# atarimovie.net
KiCad netlist of a schematic drawn in EAGLE
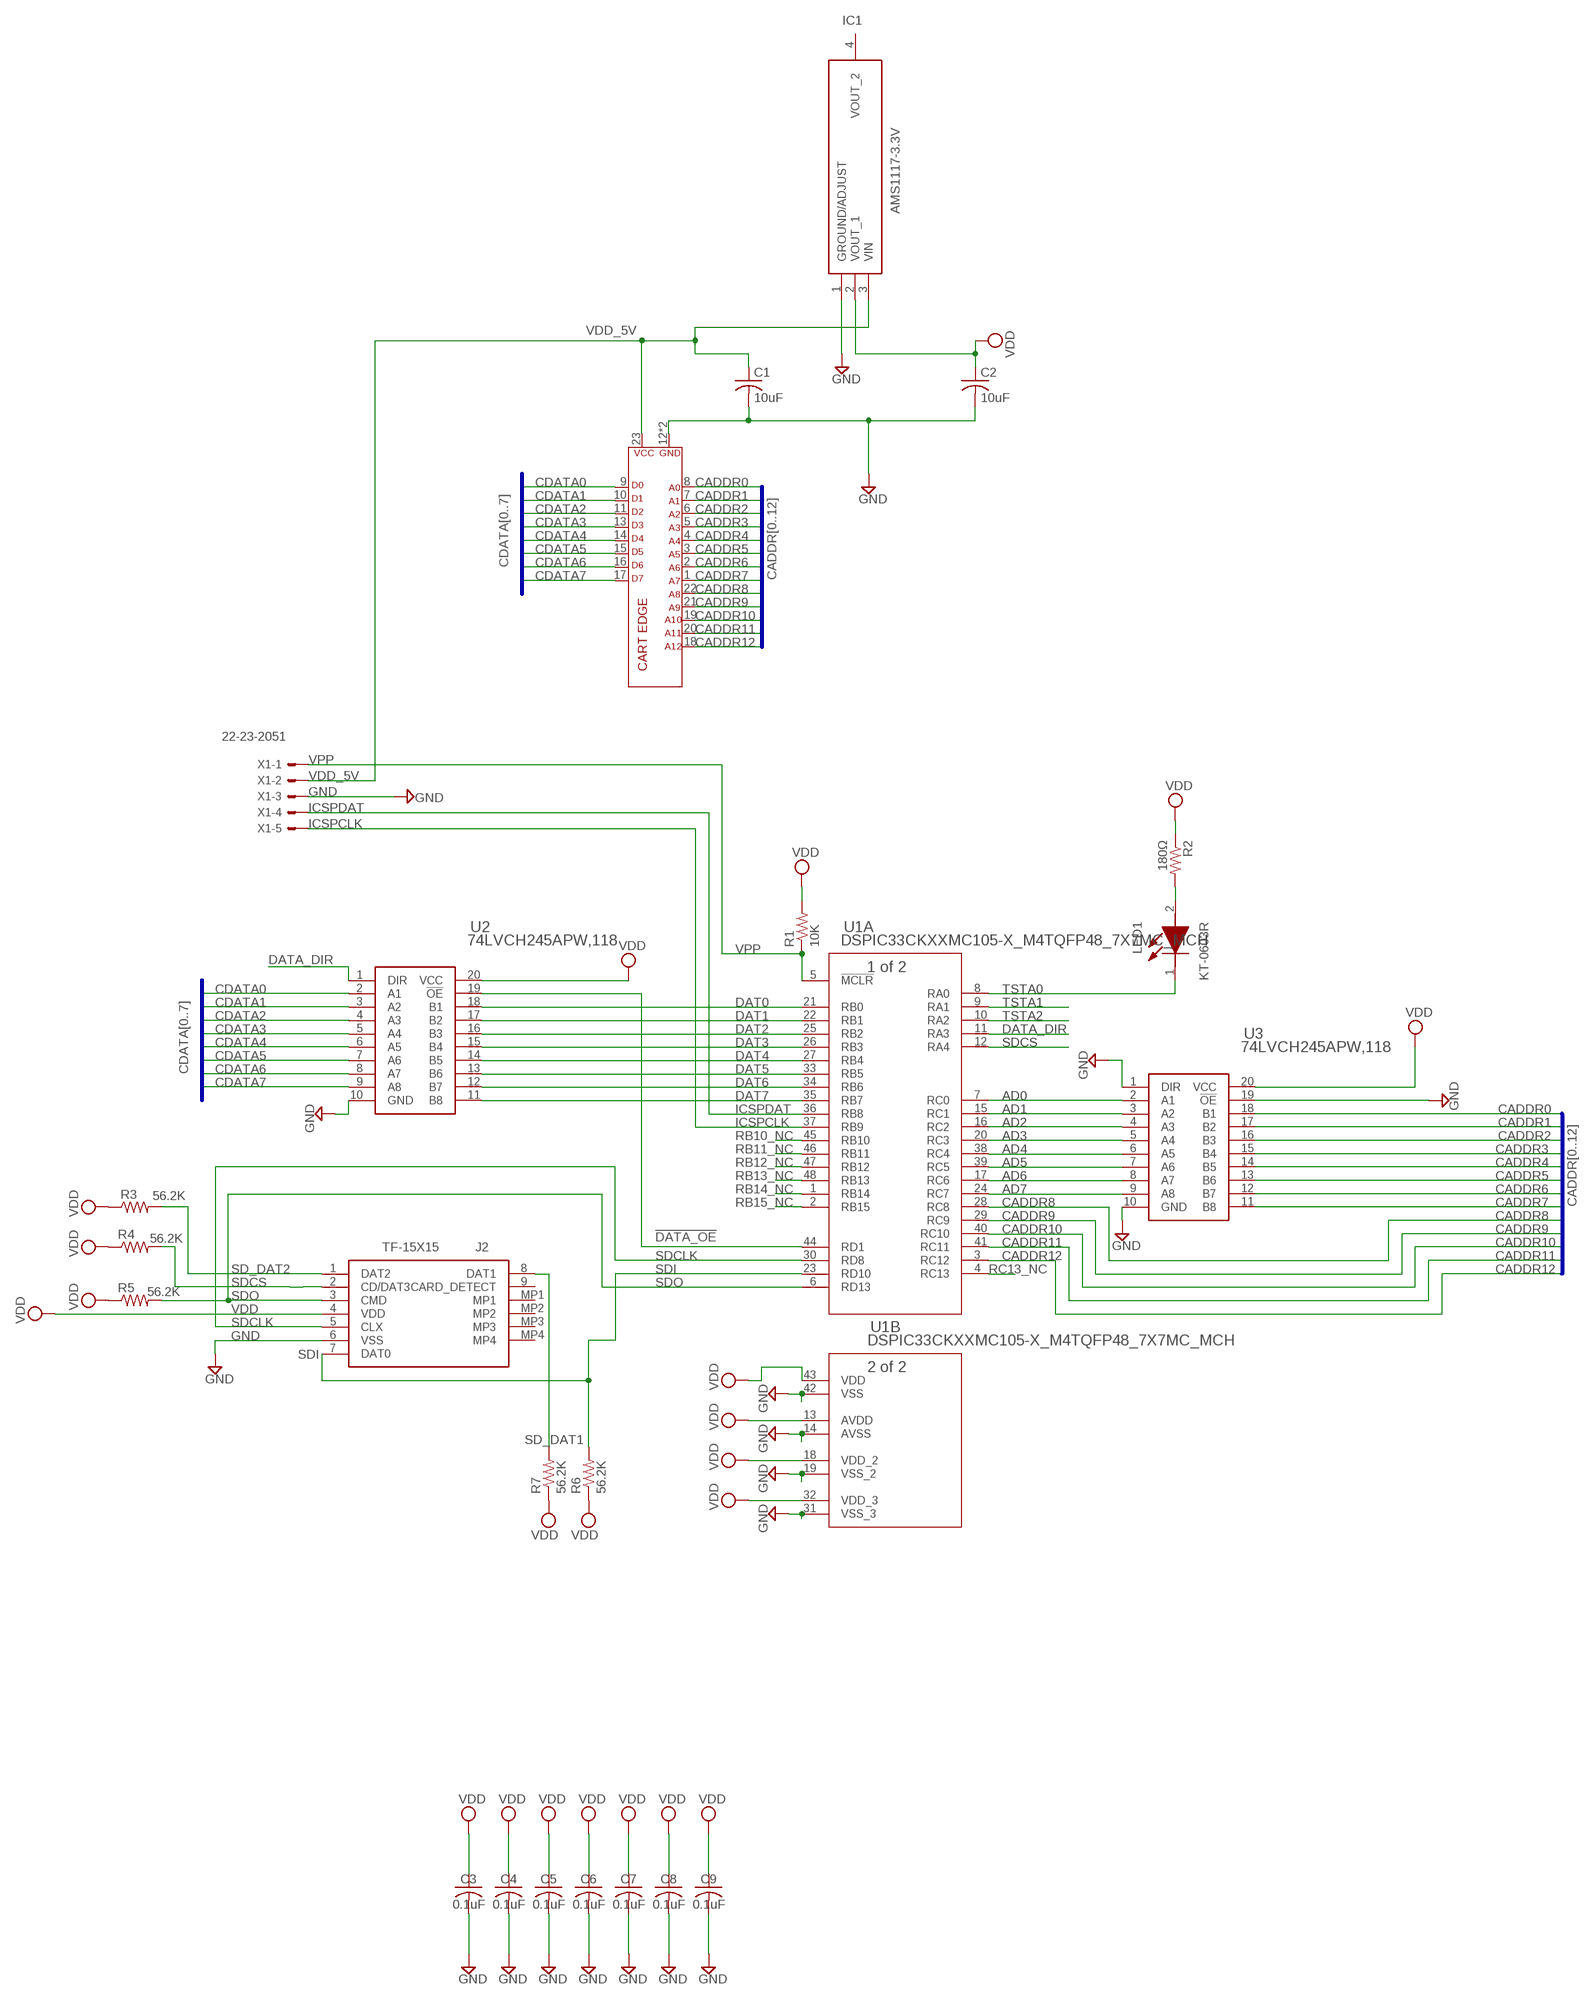
[diagram p0: schematic, sheet 1]

(export (version "E")
  (design (tool "Eeschema 10.0.6"))
  (components
    (comp (ref "C1")
      (value "10uF")
      (footprint "eagle-import:C0603K")
      (libsource (lib "eagle-import") (part "C-USC0603K"))
    )
    (comp (ref "C2")
      (value "10uF")
      (footprint "eagle-import:C0603K")
      (libsource (lib "eagle-import") (part "C-USC0603K"))
    )
    (comp (ref "C3")
      (value "0.1uF")
      (footprint "eagle-import:C0603K")
      (libsource (lib "eagle-import") (part "C-USC0603K"))
    )
    (comp (ref "C4")
      (value "0.1uF")
      (footprint "eagle-import:C0603K")
      (libsource (lib "eagle-import") (part "C-USC0603K"))
    )
    (comp (ref "C5")
      (value "0.1uF")
      (footprint "eagle-import:C0603K")
      (libsource (lib "eagle-import") (part "C-USC0603K"))
    )
    (comp (ref "C6")
      (value "0.1uF")
      (footprint "eagle-import:C0603K")
      (libsource (lib "eagle-import") (part "C-USC0603K"))
    )
    (comp (ref "C7")
      (value "0.1uF")
      (footprint "eagle-import:C0603K")
      (libsource (lib "eagle-import") (part "C-USC0603K"))
    )
    (comp (ref "C8")
      (value "0.1uF")
      (footprint "eagle-import:C0603K")
      (libsource (lib "eagle-import") (part "C-USC0603K"))
    )
    (comp (ref "C9")
      (value "0.1uF")
      (footprint "eagle-import:C0603K")
      (libsource (lib "eagle-import") (part "C-USC0603K"))
    )
    (comp (ref "IC1")
      (value "AMS1117-3.3V")
      (footprint "eagle-import:SOT229P700X180-4N")
      (fields (field (name "MANUFACTURER_PART_NUMBER") "ams1117-3.3v"))
      (libsource (lib "eagle-import") (part "AMS1117-3.3V"))
    )
    (comp (ref "J1")
      (value "CARTRIDGE EDGE")
      (footprint "eagle-import:MED_TABS_SHORT")
      (libsource (lib "eagle-import") (part "ATARI-2600MED_TABS_SHORT"))
    )
    (comp (ref "J2")
      (value "TF-15X15")
      (footprint "eagle-import:TF15X15")
      (libsource (lib "eagle-import") (part "TF-15X15"))
    )
    (comp (ref "LED1")
      (value "KT-0603R")
      (footprint "eagle-import:LEDC1608X70N")
      (libsource (lib "eagle-import") (part "KT-0603R"))
    )
    (comp (ref "R1")
      (value "10K")
      (footprint "eagle-import:R0603")
      (libsource (lib "eagle-import") (part "R-US_R0603"))
    )
    (comp (ref "R2")
      (value "180Ω")
      (footprint "eagle-import:R0603")
      (libsource (lib "eagle-import") (part "R-US_R0603"))
    )
    (comp (ref "R3")
      (value "56.2K")
      (footprint "eagle-import:R0603")
      (libsource (lib "eagle-import") (part "R-US_R0603"))
    )
    (comp (ref "R4")
      (value "56.2K")
      (footprint "eagle-import:R0603")
      (libsource (lib "eagle-import") (part "R-US_R0603"))
    )
    (comp (ref "R5")
      (value "56.2K")
      (footprint "eagle-import:R0603")
      (libsource (lib "eagle-import") (part "R-US_R0603"))
    )
    (comp (ref "R6")
      (value "56.2K")
      (footprint "eagle-import:R0603")
      (libsource (lib "eagle-import") (part "R-US_R0603"))
    )
    (comp (ref "R7")
      (value "56.2K")
      (footprint "eagle-import:R0603")
      (libsource (lib "eagle-import") (part "R-US_R0603"))
    )
    (comp (ref "U1")
      (value "DSPIC33CKXXMC105-X_M4TQFP48_7X7MC_MCH")
      (footprint "eagle-import:TQFP48_7X7MC_MCH")
      (libsource (lib "eagle-import") (part "DSPIC33CKXXMC105-X_M4TQFP48_7X7MC_MCH"))
    )
    (comp (ref "U2")
      (value "74LVCH245APW,118")
      (footprint "eagle-import:SOP65P640X110-20N")
      (fields (field (name "MOUSER_PART_NUMBER") "771-74LVCH245APW-T"))
      (libsource (lib "eagle-import") (part "74LVCH245APW,118"))
    )
    (comp (ref "U3")
      (value "74LVCH245APW,118")
      (footprint "eagle-import:SOP65P640X110-20N")
      (fields (field (name "MOUSER_PART_NUMBER") "771-74LVCH245APW-T"))
      (libsource (lib "eagle-import") (part "74LVCH245APW,118"))
    )
    (comp (ref "X1")
      (value "22-23-2051")
      (footprint "eagle-import:22-23-2051")
      (fields (field (name "MF") "MOLEX"))
      (libsource (lib "eagle-import") (part "22-23-2051"))
    )
  )
  (nets
    (net (code "1") (name "/AD0") (class "Default")
      (node (ref "U1") (pin "7") (pinfunction "RC0_7") (pintype "bidirectional"))
      (node (ref "U3") (pin "2") (pinfunction "A1_2") (pintype "bidirectional"))
    )
    (net (code "2") (name "/AD1") (class "Default")
      (node (ref "U1") (pin "15") (pinfunction "RC1_15") (pintype "bidirectional"))
      (node (ref "U3") (pin "3") (pinfunction "A2_3") (pintype "bidirectional"))
    )
    (net (code "3") (name "/AD2") (class "Default")
      (node (ref "U1") (pin "16") (pinfunction "RC2_16") (pintype "bidirectional"))
      (node (ref "U3") (pin "4") (pinfunction "A3_4") (pintype "bidirectional"))
    )
    (net (code "4") (name "/AD3") (class "Default")
      (node (ref "U1") (pin "20") (pinfunction "RC3_20") (pintype "bidirectional"))
      (node (ref "U3") (pin "5") (pinfunction "A4_5") (pintype "bidirectional"))
    )
    (net (code "5") (name "/AD4") (class "Default")
      (node (ref "U1") (pin "38") (pinfunction "RC4_38") (pintype "bidirectional"))
      (node (ref "U3") (pin "6") (pinfunction "A5_6") (pintype "bidirectional"))
    )
    (net (code "6") (name "/AD5") (class "Default")
      (node (ref "U1") (pin "39") (pinfunction "RC5_39") (pintype "bidirectional"))
      (node (ref "U3") (pin "7") (pinfunction "A6_7") (pintype "bidirectional"))
    )
    (net (code "7") (name "/AD6") (class "Default")
      (node (ref "U1") (pin "17") (pinfunction "RC6_17") (pintype "bidirectional"))
      (node (ref "U3") (pin "8") (pinfunction "A7_8") (pintype "bidirectional"))
    )
    (net (code "8") (name "/AD7") (class "Default")
      (node (ref "U1") (pin "24") (pinfunction "RC7_24") (pintype "bidirectional"))
      (node (ref "U3") (pin "9") (pinfunction "A8_9") (pintype "bidirectional"))
    )
    (net (code "9") (name "/CADDR0") (class "Default")
      (node (ref "J1") (pin "8") (pinfunction "A0_8") (pintype "bidirectional"))
      (node (ref "U3") (pin "18") (pinfunction "B1_18") (pintype "bidirectional"))
    )
    (net (code "10") (name "/CADDR1") (class "Default")
      (node (ref "J1") (pin "7") (pinfunction "A1_7") (pintype "bidirectional"))
      (node (ref "U3") (pin "17") (pinfunction "B2_17") (pintype "bidirectional"))
    )
    (net (code "11") (name "/CADDR2") (class "Default")
      (node (ref "J1") (pin "6") (pinfunction "A2_6") (pintype "bidirectional"))
      (node (ref "U3") (pin "16") (pinfunction "B3_16") (pintype "bidirectional"))
    )
    (net (code "12") (name "/CADDR3") (class "Default")
      (node (ref "J1") (pin "5") (pinfunction "A3_5") (pintype "bidirectional"))
      (node (ref "U3") (pin "15") (pinfunction "B4_15") (pintype "bidirectional"))
    )
    (net (code "13") (name "/CADDR4") (class "Default")
      (node (ref "J1") (pin "4") (pinfunction "A4_4") (pintype "bidirectional"))
      (node (ref "U3") (pin "14") (pinfunction "B5_14") (pintype "bidirectional"))
    )
    (net (code "14") (name "/CADDR5") (class "Default")
      (node (ref "J1") (pin "3") (pinfunction "A5_3") (pintype "bidirectional"))
      (node (ref "U3") (pin "13") (pinfunction "B6_13") (pintype "bidirectional"))
    )
    (net (code "15") (name "/CADDR6") (class "Default")
      (node (ref "J1") (pin "2") (pinfunction "A6_2") (pintype "bidirectional"))
      (node (ref "U3") (pin "12") (pinfunction "B7_12") (pintype "bidirectional"))
    )
    (net (code "16") (name "/CADDR7") (class "Default")
      (node (ref "J1") (pin "1") (pinfunction "A7_1") (pintype "bidirectional"))
      (node (ref "U3") (pin "11") (pinfunction "B8_11") (pintype "bidirectional"))
    )
    (net (code "17") (name "/CADDR8") (class "Default")
      (node (ref "J1") (pin "22") (pinfunction "A8_22") (pintype "bidirectional"))
      (node (ref "U1") (pin "28") (pinfunction "RC8_28") (pintype "bidirectional"))
    )
    (net (code "18") (name "/CADDR9") (class "Default")
      (node (ref "J1") (pin "21") (pinfunction "A9_21") (pintype "bidirectional"))
      (node (ref "U1") (pin "29") (pinfunction "RC9_29") (pintype "bidirectional"))
    )
    (net (code "19") (name "/CADDR10") (class "Default")
      (node (ref "J1") (pin "19") (pinfunction "A10_19") (pintype "bidirectional"))
      (node (ref "U1") (pin "40") (pinfunction "RC10_40") (pintype "bidirectional"))
    )
    (net (code "20") (name "/CADDR11") (class "Default")
      (node (ref "J1") (pin "20") (pinfunction "A11_20") (pintype "bidirectional"))
      (node (ref "U1") (pin "41") (pinfunction "RC11_41") (pintype "bidirectional"))
    )
    (net (code "21") (name "/CADDR12") (class "Default")
      (node (ref "J1") (pin "18") (pinfunction "A12_18") (pintype "bidirectional"))
      (node (ref "U1") (pin "3") (pinfunction "RC12_3") (pintype "bidirectional"))
    )
    (net (code "23") (name "/CDATA0") (class "Default")
      (node (ref "J1") (pin "9") (pinfunction "D0_9") (pintype "bidirectional"))
      (node (ref "U2") (pin "2") (pinfunction "A1_2") (pintype "bidirectional"))
    )
    (net (code "24") (name "/CDATA1") (class "Default")
      (node (ref "J1") (pin "10") (pinfunction "D1_10") (pintype "bidirectional"))
      (node (ref "U2") (pin "3") (pinfunction "A2_3") (pintype "bidirectional"))
    )
    (net (code "25") (name "/CDATA2") (class "Default")
      (node (ref "J1") (pin "11") (pinfunction "D2_11") (pintype "bidirectional"))
      (node (ref "U2") (pin "4") (pinfunction "A3_4") (pintype "bidirectional"))
    )
    (net (code "26") (name "/CDATA3") (class "Default")
      (node (ref "J1") (pin "13") (pinfunction "D3_13") (pintype "bidirectional"))
      (node (ref "U2") (pin "5") (pinfunction "A4_5") (pintype "bidirectional"))
    )
    (net (code "27") (name "/CDATA4") (class "Default")
      (node (ref "J1") (pin "14") (pinfunction "D4_14") (pintype "bidirectional"))
      (node (ref "U2") (pin "6") (pinfunction "A5_6") (pintype "bidirectional"))
    )
    (net (code "28") (name "/CDATA5") (class "Default")
      (node (ref "J1") (pin "15") (pinfunction "D5_15") (pintype "bidirectional"))
      (node (ref "U2") (pin "7") (pinfunction "A6_7") (pintype "bidirectional"))
    )
    (net (code "29") (name "/CDATA6") (class "Default")
      (node (ref "J1") (pin "16") (pinfunction "D6_16") (pintype "bidirectional"))
      (node (ref "U2") (pin "8") (pinfunction "A7_8") (pintype "bidirectional"))
    )
    (net (code "30") (name "/CDATA7") (class "Default")
      (node (ref "J1") (pin "17") (pinfunction "D7_17") (pintype "bidirectional"))
      (node (ref "U2") (pin "9") (pinfunction "A8_9") (pintype "bidirectional"))
    )
    (net (code "32") (name "/DAT0") (class "Default")
      (node (ref "U1") (pin "21") (pinfunction "RB0_21") (pintype "bidirectional"))
      (node (ref "U2") (pin "18") (pinfunction "B1_18") (pintype "bidirectional"))
    )
    (net (code "33") (name "/DAT1") (class "Default")
      (node (ref "U1") (pin "22") (pinfunction "RB1_22") (pintype "bidirectional"))
      (node (ref "U2") (pin "17") (pinfunction "B2_17") (pintype "bidirectional"))
    )
    (net (code "34") (name "/DAT2") (class "Default")
      (node (ref "U1") (pin "25") (pinfunction "RB2_25") (pintype "bidirectional"))
      (node (ref "U2") (pin "16") (pinfunction "B3_16") (pintype "bidirectional"))
    )
    (net (code "35") (name "/DAT3") (class "Default")
      (node (ref "U1") (pin "26") (pinfunction "RB3_26") (pintype "bidirectional"))
      (node (ref "U2") (pin "15") (pinfunction "B4_15") (pintype "bidirectional"))
    )
    (net (code "36") (name "/DAT4") (class "Default")
      (node (ref "U1") (pin "27") (pinfunction "RB4_27") (pintype "bidirectional"))
      (node (ref "U2") (pin "14") (pinfunction "B5_14") (pintype "bidirectional"))
    )
    (net (code "37") (name "/DAT5") (class "Default")
      (node (ref "U1") (pin "33") (pinfunction "RB5_33") (pintype "bidirectional"))
      (node (ref "U2") (pin "13") (pinfunction "B6_13") (pintype "bidirectional"))
    )
    (net (code "38") (name "/DAT6") (class "Default")
      (node (ref "U1") (pin "34") (pinfunction "RB6_34") (pintype "bidirectional"))
      (node (ref "U2") (pin "12") (pinfunction "B7_12") (pintype "bidirectional"))
    )
    (net (code "39") (name "/DAT7") (class "Default")
      (node (ref "U1") (pin "35") (pinfunction "RB7_35") (pintype "bidirectional"))
      (node (ref "U2") (pin "11") (pinfunction "B8_11") (pintype "bidirectional"))
    )
    (net (code "40") (name "/DATA_DIR") (class "Default")
      (node (ref "U1") (pin "11") (pinfunction "RA3_11") (pintype "bidirectional"))
      (node (ref "U2") (pin "1") (pinfunction "DIR_1") (pintype "bidirectional"))
    )
    (net (code "41") (name "/ICSPCLK") (class "Default")
      (node (ref "U1") (pin "37") (pinfunction "RB9_37") (pintype "bidirectional"))
      (node (ref "X1") (pin "5") (pinfunction "S_5") (pintype "passive"))
    )
    (net (code "42") (name "/ICSPDAT") (class "Default")
      (node (ref "U1") (pin "36") (pinfunction "RB8_36") (pintype "bidirectional"))
      (node (ref "X1") (pin "4") (pinfunction "S_4") (pintype "passive"))
    )
    (net (code "43") (name "/RB10_NC") (class "Default")
      (node (ref "U1") (pin "45") (pinfunction "RB10_45") (pintype "bidirectional"))
    )
    (net (code "44") (name "/RB11_NC") (class "Default")
      (node (ref "U1") (pin "46") (pinfunction "RB11_46") (pintype "bidirectional"))
    )
    (net (code "45") (name "/RB12_NC") (class "Default")
      (node (ref "U1") (pin "47") (pinfunction "RB12_47") (pintype "bidirectional"))
    )
    (net (code "46") (name "/RB13_NC") (class "Default")
      (node (ref "U1") (pin "48") (pinfunction "RB13_48") (pintype "bidirectional"))
    )
    (net (code "47") (name "/RB14_NC") (class "Default")
      (node (ref "U1") (pin "1") (pinfunction "RB14_1") (pintype "bidirectional"))
    )
    (net (code "48") (name "/RB15_NC") (class "Default")
      (node (ref "U1") (pin "2") (pinfunction "RB15_2") (pintype "bidirectional"))
    )
    (net (code "49") (name "/RC13_NC") (class "Default")
      (node (ref "U1") (pin "4") (pinfunction "RC13_4") (pintype "bidirectional"))
    )
    (net (code "50") (name "/SDCLK") (class "Default")
      (node (ref "J2") (pin "5") (pinfunction "CLX_5") (pintype "bidirectional"))
      (node (ref "U1") (pin "30") (pinfunction "RD8_30") (pintype "bidirectional"))
    )
    (net (code "51") (name "/SDCS") (class "Default")
      (node (ref "J2") (pin "2") (pinfunction "CD/DAT3_2") (pintype "bidirectional"))
      (node (ref "R4") (pin "2") (pinfunction "2_2") (pintype "passive"))
      (node (ref "U1") (pin "12") (pinfunction "RA4_12") (pintype "bidirectional"))
    )
    (net (code "52") (name "/SDI") (class "Default")
      (node (ref "J2") (pin "7") (pinfunction "DAT0_7") (pintype "bidirectional"))
      (node (ref "R6") (pin "2") (pinfunction "2_2") (pintype "passive"))
      (node (ref "U1") (pin "23") (pinfunction "RD10_23") (pintype "bidirectional"))
    )
    (net (code "53") (name "/SDO") (class "Default")
      (node (ref "J2") (pin "3") (pinfunction "CMD_3") (pintype "bidirectional"))
      (node (ref "R5") (pin "2") (pinfunction "2_2") (pintype "passive"))
      (node (ref "U1") (pin "6") (pinfunction "RD13_6") (pintype "bidirectional"))
    )
    (net (code "54") (name "/SD_DAT1") (class "Default")
      (node (ref "J2") (pin "8") (pinfunction "DAT1_8") (pintype "bidirectional"))
      (node (ref "R7") (pin "2") (pinfunction "2_2") (pintype "passive"))
    )
    (net (code "55") (name "/SD_DAT2") (class "Default")
      (node (ref "J2") (pin "1") (pinfunction "DAT2_1") (pintype "bidirectional"))
      (node (ref "R3") (pin "2") (pinfunction "2_2") (pintype "passive"))
    )
    (net (code "56") (name "/TSTA0") (class "Default")
      (node (ref "LED1") (pin "1") (pinfunction "K_1") (pintype "bidirectional"))
      (node (ref "U1") (pin "8") (pinfunction "RA0_8") (pintype "bidirectional"))
    )
    (net (code "57") (name "/TSTA1") (class "Default")
      (node (ref "U1") (pin "9") (pinfunction "RA1_9") (pintype "bidirectional"))
    )
    (net (code "58") (name "/TSTA2") (class "Default")
      (node (ref "U1") (pin "10") (pinfunction "RA2_10") (pintype "bidirectional"))
    )
    (net (code "59") (name "/VDD_5V") (class "Default")
      (node (ref "C1") (pin "1") (pinfunction "1_1") (pintype "passive"))
      (node (ref "IC1") (pin "3") (pinfunction "VIN_3") (pintype "bidirectional"))
      (node (ref "J1") (pin "23") (pinfunction "VCC_23") (pintype "power_in"))
      (node (ref "X1") (pin "2") (pinfunction "S_2") (pintype "passive"))
    )
    (net (code "60") (name "/VPP") (class "Default")
      (node (ref "R1") (pin "1") (pinfunction "1_1") (pintype "passive"))
      (node (ref "U1") (pin "5") (pinfunction "~{MCLR}_5") (pintype "input"))
      (node (ref "X1") (pin "1") (pinfunction "S_1") (pintype "passive"))
    )
    (net (code "61") (name "/~{DATA_OE}") (class "Default")
      (node (ref "U1") (pin "44") (pinfunction "RD1_44") (pintype "bidirectional"))
      (node (ref "U2") (pin "19") (pinfunction "~{OE}_19") (pintype "bidirectional"))
    )
    (net (code "62") (name "GND") (class "Default")
      (node (ref "C1") (pin "2") (pinfunction "2_2") (pintype "passive"))
      (node (ref "C2") (pin "2") (pinfunction "2_2") (pintype "passive"))
      (node (ref "C3") (pin "2") (pinfunction "2_2") (pintype "passive"))
      (node (ref "C4") (pin "2") (pinfunction "2_2") (pintype "passive"))
      (node (ref "C5") (pin "2") (pinfunction "2_2") (pintype "passive"))
      (node (ref "C6") (pin "2") (pinfunction "2_2") (pintype "passive"))
      (node (ref "C7") (pin "2") (pinfunction "2_2") (pintype "passive"))
      (node (ref "C8") (pin "2") (pinfunction "2_2") (pintype "passive"))
      (node (ref "C9") (pin "2") (pinfunction "2_2") (pintype "passive"))
      (node (ref "IC1") (pin "1") (pinfunction "GROUND/ADJUST_1") (pintype "bidirectional"))
      (node (ref "J1") (pin "12") (pinfunction "GND_12") (pintype "power_in"))
      (node (ref "J1") (pin "24") (pinfunction "GND_24") (pintype "power_in"))
      (node (ref "J2") (pin "6") (pinfunction "VSS_6") (pintype "bidirectional"))
      (node (ref "U1") (pin "14") (pinfunction "AVSS_14") (pintype "power_in"))
      (node (ref "U1") (pin "19") (pinfunction "VSS_2_19") (pintype "power_in"))
      (node (ref "U1") (pin "31") (pinfunction "VSS_3_31") (pintype "power_in"))
      (node (ref "U1") (pin "42") (pinfunction "VSS_42") (pintype "power_in"))
      (node (ref "U2") (pin "10") (pinfunction "GND_10") (pintype "bidirectional"))
      (node (ref "U3") (pin "1") (pinfunction "DIR_1") (pintype "bidirectional"))
      (node (ref "U3") (pin "10") (pinfunction "GND_10") (pintype "bidirectional"))
      (node (ref "U3") (pin "19") (pinfunction "~{OE}_19") (pintype "bidirectional"))
      (node (ref "X1") (pin "3") (pinfunction "S_3") (pintype "passive"))
    )
    (net (code "63") (name "Net-(LED1-A)") (class "Default")
      (node (ref "LED1") (pin "2") (pinfunction "A_2") (pintype "bidirectional"))
      (node (ref "R2") (pin "2") (pinfunction "2_2") (pintype "passive"))
    )
    (net (code "64") (name "VDD") (class "Default")
      (node (ref "C2") (pin "1") (pinfunction "1_1") (pintype "passive"))
      (node (ref "C3") (pin "1") (pinfunction "1_1") (pintype "passive"))
      (node (ref "C4") (pin "1") (pinfunction "1_1") (pintype "passive"))
      (node (ref "C5") (pin "1") (pinfunction "1_1") (pintype "passive"))
      (node (ref "C6") (pin "1") (pinfunction "1_1") (pintype "passive"))
      (node (ref "C7") (pin "1") (pinfunction "1_1") (pintype "passive"))
      (node (ref "C8") (pin "1") (pinfunction "1_1") (pintype "passive"))
      (node (ref "C9") (pin "1") (pinfunction "1_1") (pintype "passive"))
      (node (ref "IC1") (pin "2") (pinfunction "VOUT_1_2") (pintype "bidirectional"))
      (node (ref "J2") (pin "4") (pinfunction "VDD_4") (pintype "bidirectional"))
      (node (ref "R1") (pin "2") (pinfunction "2_2") (pintype "passive"))
      (node (ref "R2") (pin "1") (pinfunction "1_1") (pintype "passive"))
      (node (ref "R3") (pin "1") (pinfunction "1_1") (pintype "passive"))
      (node (ref "R4") (pin "1") (pinfunction "1_1") (pintype "passive"))
      (node (ref "R5") (pin "1") (pinfunction "1_1") (pintype "passive"))
      (node (ref "R6") (pin "1") (pinfunction "1_1") (pintype "passive"))
      (node (ref "R7") (pin "1") (pinfunction "1_1") (pintype "passive"))
      (node (ref "U1") (pin "13") (pinfunction "AVDD_13") (pintype "power_in"))
      (node (ref "U1") (pin "18") (pinfunction "VDD_2_18") (pintype "power_in"))
      (node (ref "U1") (pin "32") (pinfunction "VDD_3_32") (pintype "power_in"))
      (node (ref "U1") (pin "43") (pinfunction "VDD_43") (pintype "power_in"))
      (node (ref "U2") (pin "20") (pinfunction "VCC_20") (pintype "bidirectional"))
      (node (ref "U3") (pin "20") (pinfunction "VCC_20") (pintype "bidirectional"))
    )
    (net (code "65") (name "unconnected-(IC1-VOUT_2-Pad4)") (class "Default")
      (node (ref "IC1") (pin "4") (pinfunction "VOUT_2_4") (pintype "bidirectional"))
    )
    (net (code "66") (name "unconnected-(J2-CARD_DETECT-Pad9)") (class "Default")
      (node (ref "J2") (pin "9") (pinfunction "CARD_DETECT_9") (pintype "bidirectional"))
    )
    (net (code "67") (name "unconnected-(J2-PadMP1)") (class "Default")
      (node (ref "J2") (pin "MP1") (pinfunction "MP1_MP1") (pintype "bidirectional"))
    )
    (net (code "68") (name "unconnected-(J2-PadMP2)") (class "Default")
      (node (ref "J2") (pin "MP2") (pinfunction "MP2_MP2") (pintype "bidirectional"))
    )
    (net (code "69") (name "unconnected-(J2-PadMP3)") (class "Default")
      (node (ref "J2") (pin "MP3") (pinfunction "MP3_MP3") (pintype "bidirectional"))
    )
    (net (code "70") (name "unconnected-(J2-PadMP4)") (class "Default")
      (node (ref "J2") (pin "MP4") (pinfunction "MP4_MP4") (pintype "bidirectional"))
    )
  )
)
